# mini-mite.net
KiCad netlist of a schematic drawn in EAGLE
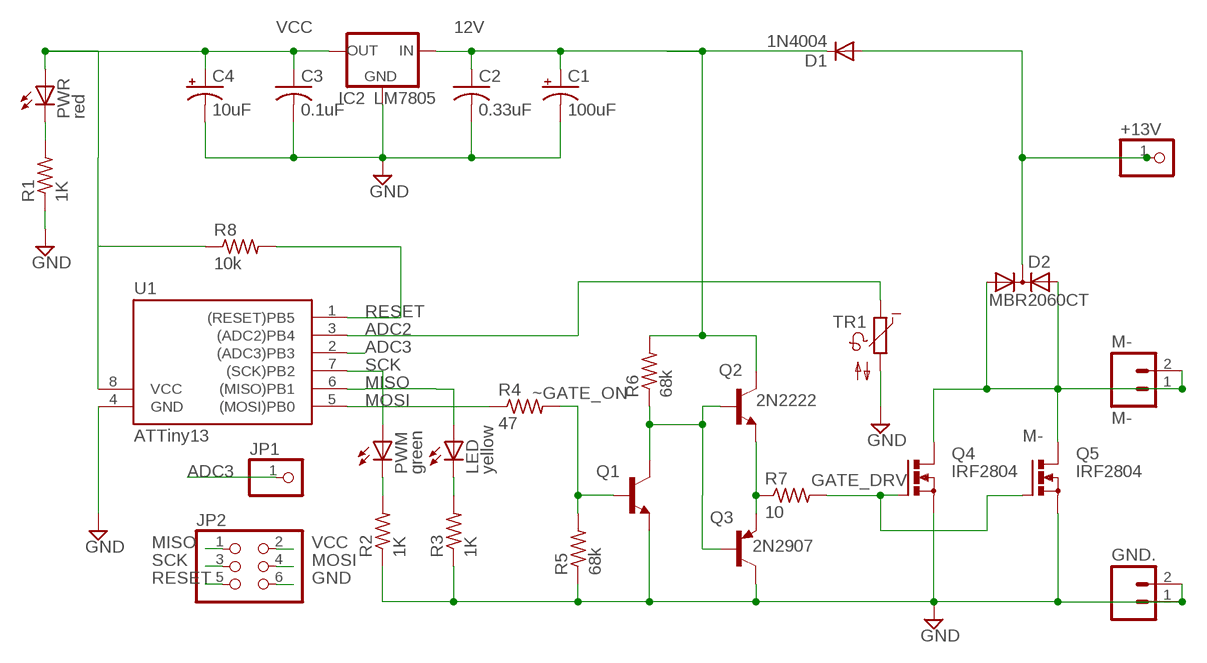
[diagram p0: schematic, sheet 1]

(export (version "E")
  (design (tool "Eeschema 10.0.6"))
  (components
    (comp (ref "+13V")
      (value "PINHD-1X1")
      (footprint "eagle-import:1X01")
      (libsource (lib "eagle-import") (part "PINHD-1X1"))
    )
    (comp (ref "C1")
      (value "100uF")
      (footprint "eagle-import:E2,5-6")
      (libsource (lib "eagle-import") (part "CPOL-USE2.5-6"))
    )
    (comp (ref "C2")
      (value "0.33uF")
      (footprint "eagle-import:C025-025X050")
      (libsource (lib "eagle-import") (part "C-US025-025X050"))
    )
    (comp (ref "C3")
      (value "0.1uF")
      (footprint "eagle-import:C025-025X050")
      (libsource (lib "eagle-import") (part "C-US025-025X050"))
    )
    (comp (ref "C4")
      (value "10uF")
      (footprint "eagle-import:E2,5-6")
      (libsource (lib "eagle-import") (part "CPOL-USE2.5-6"))
    )
    (comp (ref "D1")
      (value "1N4004")
      (footprint "eagle-import:DO41-10")
      (libsource (lib "eagle-import") (part "1N4004"))
    )
    (comp (ref "D2")
      (value "MBR2060CT")
      (footprint "eagle-import:TO220ABS")
      (libsource (lib "eagle-import") (part "DIODE-2AC|CATO220V"))
    )
    (comp (ref "GND.")
      (value "M02LOCK_LONGPADS")
      (footprint "eagle-import:1X02_LOCK_LONGPADS")
      (libsource (lib "eagle-import") (part "M02LOCK_LONGPADS"))
    )
    (comp (ref "IC2")
      (value "LM7805")
      (footprint "eagle-import:78XXS")
      (libsource (lib "eagle-import") (part "78XXS"))
    )
    (comp (ref "JP1")
      (value "PINHD-1X1")
      (footprint "eagle-import:1X01")
      (libsource (lib "eagle-import") (part "PINHD-1X1"))
    )
    (comp (ref "JP2")
      (value "PINHD-2X3")
      (footprint "eagle-import:2X03")
      (libsource (lib "eagle-import") (part "PINHD-2X3"))
    )
    (comp (ref "LED")
      (value "yellow")
      (footprint "eagle-import:LED5MM")
      (libsource (lib "eagle-import") (part "LED5MM"))
    )
    (comp (ref "M-")
      (value "M-")
      (footprint "eagle-import:1X02_LOCK_LONGPADS")
      (libsource (lib "eagle-import") (part "M02LOCK_LONGPADS"))
    )
    (comp (ref "PWM")
      (value "green")
      (footprint "eagle-import:LED5MM")
      (libsource (lib "eagle-import") (part "LED5MM"))
    )
    (comp (ref "PWR")
      (value "red")
      (footprint "eagle-import:LED5MM")
      (libsource (lib "eagle-import") (part "LED5MM"))
    )
    (comp (ref "Q1")
      (value "2N2222")
      (footprint "eagle-import:TO92-EBC-OVAL")
      (libsource (lib "eagle-import") (part "2N2222"))
    )
    (comp (ref "Q2")
      (value "2N2222")
      (footprint "eagle-import:TO92-EBC-OVAL")
      (libsource (lib "eagle-import") (part "2N2222"))
    )
    (comp (ref "Q3")
      (value "2N2907")
      (footprint "eagle-import:TO92-EBC-OVAL")
      (libsource (lib "eagle-import") (part "2N2907"))
    )
    (comp (ref "Q4")
      (value "IRF2804")
      (footprint "eagle-import:TO220BV")
      (libsource (lib "eagle-import") (part "PMOSFET_NTO220BV"))
    )
    (comp (ref "Q5")
      (value "IRF2804")
      (footprint "eagle-import:TO220BV")
      (libsource (lib "eagle-import") (part "PMOSFET_NTO220BV"))
    )
    (comp (ref "R1")
      (value "1K")
      (footprint "eagle-import:0207_7")
      (libsource (lib "eagle-import") (part "R-US_0207/7"))
    )
    (comp (ref "R2")
      (value "1K")
      (footprint "eagle-import:0207_7")
      (libsource (lib "eagle-import") (part "R-US_0207/7"))
    )
    (comp (ref "R3")
      (value "1K")
      (footprint "eagle-import:0207_7")
      (libsource (lib "eagle-import") (part "R-US_0207/7"))
    )
    (comp (ref "R4")
      (value "47")
      (footprint "eagle-import:0207_10")
      (libsource (lib "eagle-import") (part "R-US_0207/10"))
    )
    (comp (ref "R5")
      (value "68k")
      (footprint "eagle-import:0207_7")
      (libsource (lib "eagle-import") (part "R-US_0207/7"))
    )
    (comp (ref "R6")
      (value "68k")
      (footprint "eagle-import:0207_7")
      (libsource (lib "eagle-import") (part "R-US_0207/7"))
    )
    (comp (ref "R7")
      (value "10")
      (footprint "eagle-import:0207_7")
      (libsource (lib "eagle-import") (part "R-US_0207/7"))
    )
    (comp (ref "R8")
      (value "10k")
      (footprint "eagle-import:0207_7")
      (libsource (lib "eagle-import") (part "R-US_0207/7"))
    )
    (comp (ref "TR1")
      (value "NTC642-6")
      (footprint "eagle-import:P642")
      (libsource (lib "eagle-import") (part "NTC642-6"))
    )
    (comp (ref "U1")
      (value "ATTiny13")
      (footprint "eagle-import:DIL08")
      (libsource (lib "eagle-import") (part "TINY138P3"))
    )
  )
  (nets
    (net (code "1") (name "/12V") (class "Default")
      (node (ref "C1") (pin "+") (pinfunction "+_+") (pintype "passive"))
      (node (ref "C2") (pin "1") (pinfunction "1_1") (pintype "passive"))
      (node (ref "D1") (pin "C") (pinfunction "C_C") (pintype "passive"))
      (node (ref "IC2") (pin "IN") (pinfunction "IN_IN") (pintype "input"))
      (node (ref "Q2") (pin "C") (pinfunction "C_C") (pintype "passive"))
      (node (ref "R6") (pin "2") (pinfunction "2_2") (pintype "passive"))
    )
    (net (code "2") (name "/ADC2") (class "Default")
      (node (ref "TR1") (pin "1") (pinfunction "1_1") (pintype "passive"))
      (node (ref "U1") (pin "3") (pinfunction "(ADC2)PB4_3") (pintype "bidirectional"))
    )
    (net (code "3") (name "/ADC3") (class "Default")
      (node (ref "JP1") (pin "1") (pinfunction "1_1") (pintype "passive"))
      (node (ref "U1") (pin "2") (pinfunction "(ADC3)PB3_2") (pintype "bidirectional"))
    )
    (net (code "4") (name "/GATE_DRV") (class "Default")
      (node (ref "Q4") (pin "G") (pinfunction "G_G") (pintype "passive"))
      (node (ref "Q5") (pin "G") (pinfunction "G_G") (pintype "passive"))
      (node (ref "R7") (pin "2") (pinfunction "2_2") (pintype "passive"))
    )
    (net (code "5") (name "/M-") (class "Default")
      (node (ref "D2") (pin "A1") (pinfunction "A1_A1") (pintype "passive"))
      (node (ref "D2") (pin "A2") (pinfunction "A2_A2") (pintype "passive"))
      (node (ref "M-") (pin "1") (pinfunction "1_1") (pintype "passive"))
      (node (ref "M-") (pin "2") (pinfunction "2_2") (pintype "passive"))
      (node (ref "Q4") (pin "D") (pinfunction "D_D") (pintype "passive"))
      (node (ref "Q5") (pin "D") (pinfunction "D_D") (pintype "passive"))
    )
    (net (code "6") (name "/MISO") (class "Default")
      (node (ref "JP2") (pin "1") (pinfunction "1_1") (pintype "passive"))
      (node (ref "LED") (pin "A") (pinfunction "A_A") (pintype "passive"))
      (node (ref "U1") (pin "6") (pinfunction "(MISO)PB1_6") (pintype "bidirectional"))
    )
    (net (code "7") (name "/MOSI") (class "Default")
      (node (ref "JP2") (pin "4") (pinfunction "4_4") (pintype "passive"))
      (node (ref "R4") (pin "1") (pinfunction "1_1") (pintype "passive"))
      (node (ref "U1") (pin "5") (pinfunction "(MOSI)PB0_5") (pintype "bidirectional"))
    )
    (net (code "8") (name "/RESET") (class "Default")
      (node (ref "JP2") (pin "5") (pinfunction "5_5") (pintype "passive"))
      (node (ref "R8") (pin "2") (pinfunction "2_2") (pintype "passive"))
      (node (ref "U1") (pin "1") (pinfunction "(RESET)PB5_1") (pintype "bidirectional"))
    )
    (net (code "9") (name "/SCK") (class "Default")
      (node (ref "JP2") (pin "3") (pinfunction "3_3") (pintype "passive"))
      (node (ref "PWM") (pin "A") (pinfunction "A_A") (pintype "passive"))
      (node (ref "U1") (pin "7") (pinfunction "(SCK)PB2_7") (pintype "bidirectional"))
    )
    (net (code "10") (name "/VCC") (class "Default")
      (node (ref "C3") (pin "1") (pinfunction "1_1") (pintype "passive"))
      (node (ref "C4") (pin "+") (pinfunction "+_+") (pintype "passive"))
      (node (ref "IC2") (pin "OUT") (pinfunction "OUT_OUT") (pintype "passive"))
      (node (ref "JP2") (pin "2") (pinfunction "2_2") (pintype "passive"))
      (node (ref "PWR") (pin "A") (pinfunction "A_A") (pintype "passive"))
      (node (ref "R8") (pin "1") (pinfunction "1_1") (pintype "passive"))
      (node (ref "U1") (pin "8") (pinfunction "VCC_8") (pintype "power_in"))
    )
    (net (code "11") (name "/~{GATE_ON}") (class "Default")
      (node (ref "Q1") (pin "B") (pinfunction "B_B") (pintype "passive"))
      (node (ref "R4") (pin "2") (pinfunction "2_2") (pintype "passive"))
      (node (ref "R5") (pin "2") (pinfunction "2_2") (pintype "passive"))
    )
    (net (code "12") (name "GND") (class "Default")
      (node (ref "C1") (pin "-") (pinfunction "-_-") (pintype "passive"))
      (node (ref "C2") (pin "2") (pinfunction "2_2") (pintype "passive"))
      (node (ref "C3") (pin "2") (pinfunction "2_2") (pintype "passive"))
      (node (ref "C4") (pin "-") (pinfunction "-_-") (pintype "passive"))
      (node (ref "GND.") (pin "1") (pinfunction "1_1") (pintype "passive"))
      (node (ref "GND.") (pin "2") (pinfunction "2_2") (pintype "passive"))
      (node (ref "IC2") (pin "GND") (pinfunction "GND_GND") (pintype "input"))
      (node (ref "JP2") (pin "6") (pinfunction "6_6") (pintype "passive"))
      (node (ref "Q1") (pin "E") (pinfunction "E_E") (pintype "passive"))
      (node (ref "Q3") (pin "C") (pinfunction "C_C") (pintype "passive"))
      (node (ref "Q4") (pin "S") (pinfunction "S_S") (pintype "passive"))
      (node (ref "Q5") (pin "S") (pinfunction "S_S") (pintype "passive"))
      (node (ref "R1") (pin "1") (pinfunction "1_1") (pintype "passive"))
      (node (ref "R2") (pin "1") (pinfunction "1_1") (pintype "passive"))
      (node (ref "R3") (pin "1") (pinfunction "1_1") (pintype "passive"))
      (node (ref "R5") (pin "1") (pinfunction "1_1") (pintype "passive"))
      (node (ref "TR1") (pin "2") (pinfunction "2_2") (pintype "passive"))
      (node (ref "U1") (pin "4") (pinfunction "GND_4") (pintype "power_in"))
    )
    (net (code "13") (name "Net-(+13V-Pad1)") (class "Default")
      (node (ref "+13V") (pin "1") (pinfunction "1_1") (pintype "passive"))
      (node (ref "D1") (pin "A") (pinfunction "A_A") (pintype "passive"))
      (node (ref "D2") (pin "C") (pinfunction "C_C") (pintype "passive"))
    )
    (net (code "14") (name "Net-(LED-C)") (class "Default")
      (node (ref "LED") (pin "K") (pinfunction "C_K") (pintype "passive"))
      (node (ref "R3") (pin "2") (pinfunction "2_2") (pintype "passive"))
    )
    (net (code "15") (name "Net-(PWM-C)") (class "Default")
      (node (ref "PWM") (pin "K") (pinfunction "C_K") (pintype "passive"))
      (node (ref "R2") (pin "2") (pinfunction "2_2") (pintype "passive"))
    )
    (net (code "16") (name "Net-(PWR-C)") (class "Default")
      (node (ref "PWR") (pin "K") (pinfunction "C_K") (pintype "passive"))
      (node (ref "R1") (pin "2") (pinfunction "2_2") (pintype "passive"))
    )
    (net (code "17") (name "Net-(Q1-PadC)") (class "Default")
      (node (ref "Q1") (pin "C") (pinfunction "C_C") (pintype "passive"))
      (node (ref "Q2") (pin "B") (pinfunction "B_B") (pintype "passive"))
      (node (ref "Q3") (pin "B") (pinfunction "B_B") (pintype "passive"))
      (node (ref "R6") (pin "1") (pinfunction "1_1") (pintype "passive"))
    )
    (net (code "18") (name "Net-(Q2-PadE)") (class "Default")
      (node (ref "Q2") (pin "E") (pinfunction "E_E") (pintype "passive"))
      (node (ref "Q3") (pin "E") (pinfunction "E_E") (pintype "passive"))
      (node (ref "R7") (pin "1") (pinfunction "1_1") (pintype "passive"))
    )
  )
)
